# Clock_Multiplexer.net
KiCad netlist of a schematic drawn in EAGLE
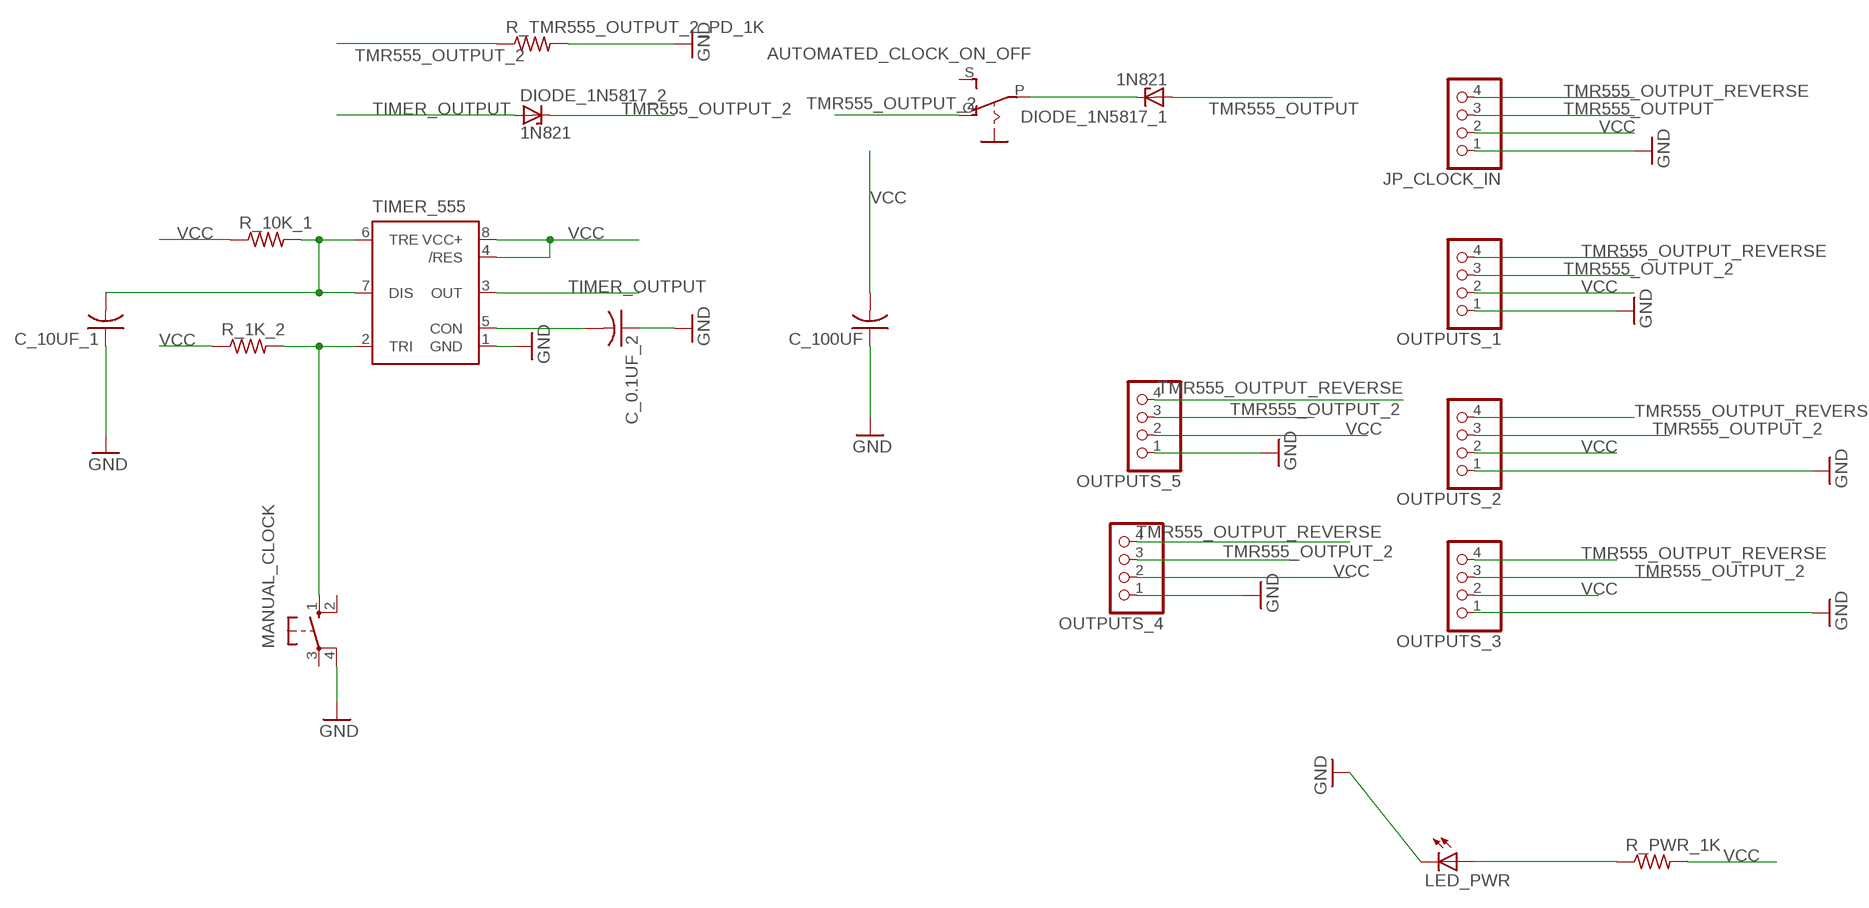
[diagram p0: schematic, sheet 1]

(export (version "E")
  (design (tool "Eeschema 10.0.6"))
  (components
    (comp (ref "AUTOMATED_CLOCK_ON_OFF")
      (value "EG1218S")
      (footprint "eagle-import:EG1218")
      (libsource (lib "eagle-import") (part "EG1218S"))
    )
    (comp (ref "C_0.1UF_2")
      (value "C-USC1206")
      (footprint "eagle-import:C1206")
      (libsource (lib "eagle-import") (part "C-USC1206"))
    )
    (comp (ref "C_10UF_1")
      (value "C-USC1206")
      (footprint "eagle-import:C1206")
      (libsource (lib "eagle-import") (part "C-USC1206"))
    )
    (comp (ref "C_100UF")
      (value "C-US025-030X050")
      (footprint "eagle-import:C025-030X050")
      (libsource (lib "eagle-import") (part "C-US025-030X050"))
    )
    (comp (ref "DIODE_1N5817_1")
      (value "1N821")
      (footprint "eagle-import:DO35Z10")
      (libsource (lib "eagle-import") (part "1N821"))
    )
    (comp (ref "DIODE_1N5817_2")
      (value "1N821")
      (footprint "eagle-import:DO35Z10")
      (libsource (lib "eagle-import") (part "1N821"))
    )
    (comp (ref "JP_CLOCK_IN")
      (value "PINHD-1X4")
      (footprint "eagle-import:1X04")
      (libsource (lib "eagle-import") (part "PINHD-1X4"))
    )
    (comp (ref "LED_PWR")
      (value "LEDSMT1206")
      (footprint "eagle-import:1206")
      (libsource (lib "eagle-import") (part "LEDSMT1206"))
    )
    (comp (ref "MANUAL_CLOCK")
      (value "10-XX")
      (footprint "eagle-import:B3F-10XX")
      (fields (field (name "MPN") "B3F-1000"))
      (libsource (lib "eagle-import") (part "10-XX"))
    )
    (comp (ref "OUTPUTS_1")
      (value "PINHD-1X4")
      (footprint "eagle-import:1X04")
      (libsource (lib "eagle-import") (part "PINHD-1X4"))
    )
    (comp (ref "OUTPUTS_2")
      (value "PINHD-1X4")
      (footprint "eagle-import:1X04")
      (libsource (lib "eagle-import") (part "PINHD-1X4"))
    )
    (comp (ref "OUTPUTS_3")
      (value "PINHD-1X4")
      (footprint "eagle-import:1X04")
      (libsource (lib "eagle-import") (part "PINHD-1X4"))
    )
    (comp (ref "OUTPUTS_4")
      (value "PINHD-1X4")
      (footprint "eagle-import:1X04")
      (libsource (lib "eagle-import") (part "PINHD-1X4"))
    )
    (comp (ref "OUTPUTS_5")
      (value "PINHD-1X4")
      (footprint "eagle-import:1X04")
      (libsource (lib "eagle-import") (part "PINHD-1X4"))
    )
    (comp (ref "R_1K_2")
      (value "R-US_R1206")
      (footprint "eagle-import:R1206")
      (libsource (lib "eagle-import") (part "R-US_R1206"))
    )
    (comp (ref "R_10K_1")
      (value "R-US_R1206")
      (footprint "eagle-import:R1206")
      (libsource (lib "eagle-import") (part "R-US_R1206"))
    )
    (comp (ref "R_PWR_1K")
      (value "R-US_R1206")
      (footprint "eagle-import:R1206")
      (libsource (lib "eagle-import") (part "R-US_R1206"))
    )
    (comp (ref "R_TMR555_OUTPUT_2_PD_1K")
      (value "R-US_R1206")
      (footprint "eagle-import:R1206")
      (libsource (lib "eagle-import") (part "R-US_R1206"))
    )
    (comp (ref "TIMER_555")
      (value "NE555D")
      (footprint "eagle-import:SO08")
      (libsource (lib "eagle-import") (part "NE555D"))
    )
  )
  (nets
    (net (code "1") (name "/TIMER_OUTPUT") (class "Default")
      (node (ref "DIODE_1N5817_2") (pin "A") (pinfunction "A_A") (pintype "passive"))
      (node (ref "TIMER_555") (pin "3") (pinfunction "OUT_3") (pintype "output"))
    )
    (net (code "2") (name "/TMR555_OUTPUT") (class "Default")
      (node (ref "DIODE_1N5817_1") (pin "A") (pinfunction "A_A") (pintype "passive"))
      (node (ref "JP_CLOCK_IN") (pin "3") (pinfunction "3_3") (pintype "passive"))
    )
    (net (code "3") (name "/TMR555_OUTPUT_2") (class "Default")
      (node (ref "AUTOMATED_CLOCK_ON_OFF") (pin "O") (pinfunction "O_O") (pintype "passive"))
      (node (ref "DIODE_1N5817_2") (pin "C") (pinfunction "C_C") (pintype "passive"))
      (node (ref "OUTPUTS_1") (pin "3") (pinfunction "3_3") (pintype "passive"))
      (node (ref "OUTPUTS_2") (pin "3") (pinfunction "3_3") (pintype "passive"))
      (node (ref "OUTPUTS_3") (pin "3") (pinfunction "3_3") (pintype "passive"))
      (node (ref "OUTPUTS_4") (pin "3") (pinfunction "3_3") (pintype "passive"))
      (node (ref "OUTPUTS_5") (pin "3") (pinfunction "3_3") (pintype "passive"))
      (node (ref "R_TMR555_OUTPUT_2_PD_1K") (pin "1") (pinfunction "1_1") (pintype "passive"))
    )
    (net (code "4") (name "/TMR555_OUTPUT_REVERSE") (class "Default")
      (node (ref "JP_CLOCK_IN") (pin "4") (pinfunction "4_4") (pintype "passive"))
      (node (ref "OUTPUTS_1") (pin "4") (pinfunction "4_4") (pintype "passive"))
      (node (ref "OUTPUTS_2") (pin "4") (pinfunction "4_4") (pintype "passive"))
      (node (ref "OUTPUTS_3") (pin "4") (pinfunction "4_4") (pintype "passive"))
      (node (ref "OUTPUTS_4") (pin "4") (pinfunction "4_4") (pintype "passive"))
      (node (ref "OUTPUTS_5") (pin "4") (pinfunction "4_4") (pintype "passive"))
    )
    (net (code "5") (name "/VCC") (class "Default")
      (node (ref "C_100UF") (pin "2") (pinfunction "2_2") (pintype "passive"))
      (node (ref "JP_CLOCK_IN") (pin "2") (pinfunction "2_2") (pintype "passive"))
      (node (ref "OUTPUTS_1") (pin "2") (pinfunction "2_2") (pintype "passive"))
      (node (ref "OUTPUTS_2") (pin "2") (pinfunction "2_2") (pintype "passive"))
      (node (ref "OUTPUTS_3") (pin "2") (pinfunction "2_2") (pintype "passive"))
      (node (ref "OUTPUTS_4") (pin "2") (pinfunction "2_2") (pintype "passive"))
      (node (ref "OUTPUTS_5") (pin "2") (pinfunction "2_2") (pintype "passive"))
      (node (ref "R_10K_1") (pin "1") (pinfunction "1_1") (pintype "passive"))
      (node (ref "R_1K_2") (pin "1") (pinfunction "1_1") (pintype "passive"))
      (node (ref "R_PWR_1K") (pin "2") (pinfunction "2_2") (pintype "passive"))
      (node (ref "TIMER_555") (pin "4") (pinfunction "/RES_4") (pintype "input"))
      (node (ref "TIMER_555") (pin "8") (pinfunction "VCC+_8") (pintype "power_in"))
    )
    (net (code "6") (name "GND") (class "Default")
      (node (ref "C_0.1UF_2") (pin "1") (pinfunction "1_1") (pintype "passive"))
      (node (ref "C_100UF") (pin "1") (pinfunction "1_1") (pintype "passive"))
      (node (ref "C_10UF_1") (pin "1") (pinfunction "1_1") (pintype "passive"))
      (node (ref "JP_CLOCK_IN") (pin "1") (pinfunction "1_1") (pintype "passive"))
      (node (ref "LED_PWR") (pin "C") (pinfunction "C_C") (pintype "passive"))
      (node (ref "MANUAL_CLOCK") (pin "4") (pinfunction "P1_4") (pintype "passive"))
      (node (ref "OUTPUTS_1") (pin "1") (pinfunction "1_1") (pintype "passive"))
      (node (ref "OUTPUTS_2") (pin "1") (pinfunction "1_1") (pintype "passive"))
      (node (ref "OUTPUTS_3") (pin "1") (pinfunction "1_1") (pintype "passive"))
      (node (ref "OUTPUTS_4") (pin "1") (pinfunction "1_1") (pintype "passive"))
      (node (ref "OUTPUTS_5") (pin "1") (pinfunction "1_1") (pintype "passive"))
      (node (ref "R_TMR555_OUTPUT_2_PD_1K") (pin "2") (pinfunction "2_2") (pintype "passive"))
      (node (ref "TIMER_555") (pin "1") (pinfunction "GND_1") (pintype "power_in"))
    )
    (net (code "7") (name "Net-(AUTOMATED_CLOCK_ON_OFF-PadP)") (class "Default")
      (node (ref "AUTOMATED_CLOCK_ON_OFF") (pin "P") (pinfunction "P_P") (pintype "passive"))
      (node (ref "DIODE_1N5817_1") (pin "C") (pinfunction "C_C") (pintype "passive"))
    )
    (net (code "8") (name "Net-(LED_PWR-PadA)") (class "Default")
      (node (ref "LED_PWR") (pin "A") (pinfunction "A_A") (pintype "passive"))
      (node (ref "R_PWR_1K") (pin "1") (pinfunction "1_1") (pintype "passive"))
    )
    (net (code "9") (name "Net-(MANUAL_CLOCK-S)") (class "Default")
      (node (ref "MANUAL_CLOCK") (pin "1") (pinfunction "S_1") (pintype "passive"))
      (node (ref "R_1K_2") (pin "2") (pinfunction "2_2") (pintype "passive"))
      (node (ref "TIMER_555") (pin "2") (pinfunction "TRI_2") (pintype "input"))
    )
    (net (code "10") (name "Net-(TIMER_555-CON)") (class "Default")
      (node (ref "C_0.1UF_2") (pin "2") (pinfunction "2_2") (pintype "passive"))
      (node (ref "TIMER_555") (pin "5") (pinfunction "CON_5") (pintype "input"))
    )
    (net (code "11") (name "Net-(TIMER_555-DIS)") (class "Default")
      (node (ref "C_10UF_1") (pin "2") (pinfunction "2_2") (pintype "passive"))
      (node (ref "R_10K_1") (pin "2") (pinfunction "2_2") (pintype "passive"))
      (node (ref "TIMER_555") (pin "6") (pinfunction "TRE_6") (pintype "input"))
      (node (ref "TIMER_555") (pin "7") (pinfunction "DIS_7") (pintype "input"))
    )
    (net (code "12") (name "unconnected-(AUTOMATED_CLOCK_ON_OFF-PadS)") (class "Default")
      (node (ref "AUTOMATED_CLOCK_ON_OFF") (pin "S") (pinfunction "S_S") (pintype "passive"))
    )
    (net (code "13") (name "unconnected-(MANUAL_CLOCK-P-Pad3)") (class "Default")
      (node (ref "MANUAL_CLOCK") (pin "3") (pinfunction "P_3") (pintype "passive"))
    )
    (net (code "14") (name "unconnected-(MANUAL_CLOCK-S1-Pad2)") (class "Default")
      (node (ref "MANUAL_CLOCK") (pin "2") (pinfunction "S1_2") (pintype "passive"))
    )
  )
)
